# boost_stage_HP.net
KiCad netlist of a schematic drawn in Altium Designer
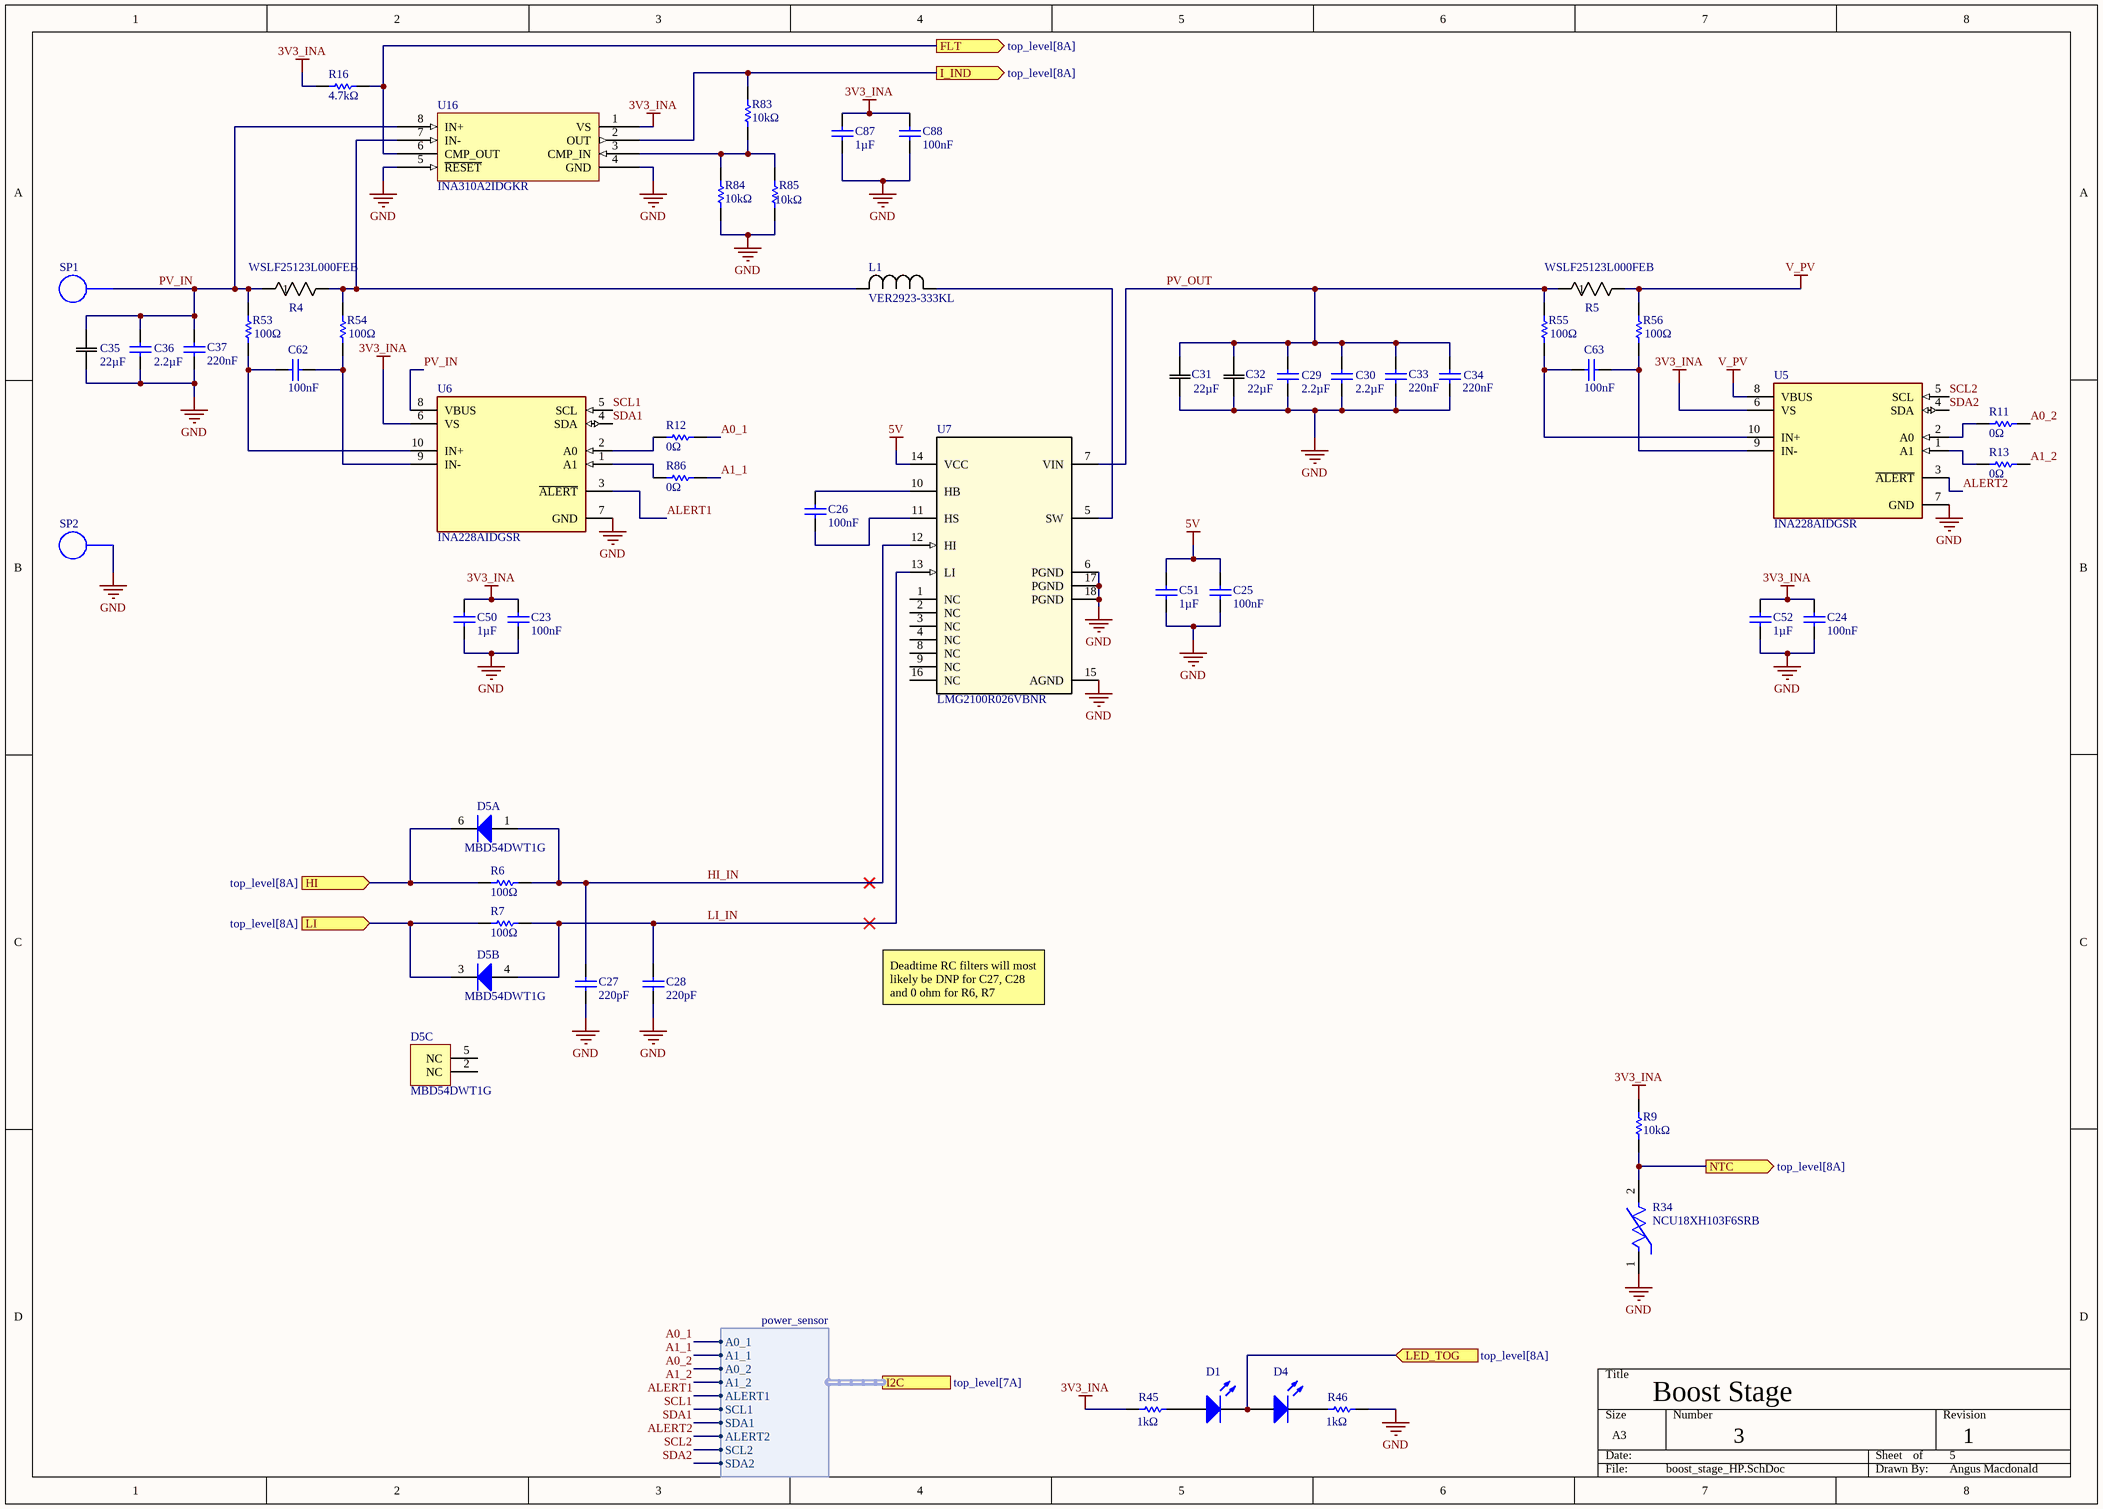
[diagram p0: boost_stage_HP.SchDoc]

(export (version "E")
  (design (tool "Eeschema 10.0.6"))
  (components
    (comp (ref "C23")
      (value "100nF")
      (footprint "C0603")
      (description "25V 100nF X7R ±10% 0603 Multilayer Ceramic Capacitors MLCC - SMD/SMT ROHS")
      (fields (field (name "TOLERANCE") "10%") (field (name "VOLTAGE") "25V"))
      (libsource (lib "Sunswift Racing") (part "Capacitor"))
    )
    (comp (ref "C24")
      (value "100nF")
      (footprint "C0603")
      (description "25V 100nF X7R ±10% 0603 Multilayer Ceramic Capacitors MLCC - SMD/SMT ROHS")
      (fields (field (name "TOLERANCE") "10%") (field (name "VOLTAGE") "25V"))
      (libsource (lib "Sunswift Racing") (part "Capacitor"))
    )
    (comp (ref "C25")
      (value "100nF")
      (footprint "C0603")
      (description "25V 100nF X7R ±10% 0603 Multilayer Ceramic Capacitors MLCC - SMD/SMT ROHS")
      (fields (field (name "TOLERANCE") "10%") (field (name "VOLTAGE") "25V"))
      (libsource (lib "Sunswift Racing") (part "Capacitor"))
    )
    (comp (ref "C26")
      (value "100nF")
      (footprint "C0603")
      (description "25V 100nF X7R ±10% 0603 Multilayer Ceramic Capacitors MLCC - SMD/SMT ROHS")
      (fields (field (name "TOLERANCE") "10%") (field (name "VOLTAGE") "25V"))
      (libsource (lib "Sunswift Racing") (part "Capacitor"))
    )
    (comp (ref "C27")
      (value "220pF")
      (footprint "C0603")
      (description "50V 220pF NP0 ±5% 0603 Multilayer Ceramic Capacitors MLCC - SMD/SMT ROHS")
      (fields (field (name "VOLTAGE") "50V") (field (name "TOLERANCE") "5%"))
      (libsource (lib "Sunswift Racing") (part "Capacitor"))
    )
    (comp (ref "C28")
      (value "220pF")
      (footprint "C0603")
      (description "50V 220pF NP0 ±5% 0603 Multilayer Ceramic Capacitors MLCC - SMD/SMT ROHS")
      (fields (field (name "VOLTAGE") "50V") (field (name "TOLERANCE") "5%"))
      (libsource (lib "Sunswift Racing") (part "Capacitor"))
    )
    (comp (ref "C29")
      (value "2.2µF")
      (footprint "FP-CC1206-1_25-IPC_B")
      (description "1206 2.2 uF 100 V ±10% Tolerance X7R SMT Multilayer Ceramic Chip Capacitor")
      (fields (field (name "TOLERANCE") "10%") (field (name "Comment") "CC1206KKX7R0BB225"))
      (libsource (lib "Sunswift Racing") (part "Copy of 11868f565c42a9108669ba33697ecf6"))
    )
    (comp (ref "C30")
      (value "2.2µF")
      (footprint "FP-CC1206-1_25-IPC_B")
      (description "1206 2.2 uF 100 V ±10% Tolerance X7R SMT Multilayer Ceramic Chip Capacitor")
      (fields (field (name "TOLERANCE") "10%") (field (name "Comment") "CC1206KKX7R0BB225"))
      (libsource (lib "Sunswift Racing") (part "Copy of 11868f565c42a9108669ba33697ecf6"))
    )
    (comp (ref "C31")
      (value "22µF")
      (footprint "CAP_EEE-FK2A220P_PAN")
      (description "Radial Can - SMD ALUMINUM ELECTROLYTIC CAPACITOR FK 100V 22muF ±20% 0.315Dia 8.00mm")
      (fields
        (field (name "TOLERANCE") "20%")
        (field (name "MANUFACTURER_PART_NUMBER") "EEE-FK2A220P")
        (field (name "COPYRIGHT") "Copyright (C) 2025 Ultra Librarian. All rights reserved.")
      )
      (libsource (lib "Sunswift Racing") (part "EEE-FK2A220P"))
    )
    (comp (ref "C32")
      (value "22µF")
      (footprint "CAP_EEE-FK2A220P_PAN")
      (description "Radial Can - SMD ALUMINUM ELECTROLYTIC CAPACITOR FK 100V 22muF ±20% 0.315Dia 8.00mm")
      (fields
        (field (name "TOLERANCE") "20%")
        (field (name "MANUFACTURER_PART_NUMBER") "EEE-FK2A220P")
        (field (name "COPYRIGHT") "Copyright (C) 2025 Ultra Librarian. All rights reserved.")
      )
      (libsource (lib "Sunswift Racing") (part "EEE-FK2A220P"))
    )
    (comp (ref "C33")
      (value "220nF")
      (footprint "C0805")
      (description "Multilayer Ceramic Capacitors MLCC - SMD/SMT 100V 0.22uF X7R 0805 10%")
      (fields
        (field (name "TOLERANCE") "10%")
        (field (name "MANUFACTURER PART NUMBER") "C2012X5R1A336M125AC")
      )
      (libsource (lib "Sunswift Racing") (part "Capacitor"))
    )
    (comp (ref "C34")
      (value "220nF")
      (footprint "C0805")
      (description "Multilayer Ceramic Capacitors MLCC - SMD/SMT 100V 0.22uF X7R 0805 10%")
      (fields
        (field (name "TOLERANCE") "10%")
        (field (name "MANUFACTURER PART NUMBER") "C2012X5R1A336M125AC")
      )
      (libsource (lib "Sunswift Racing") (part "Capacitor"))
    )
    (comp (ref "C35")
      (value "22µF")
      (footprint "CAP_EEE-FK2A220P_PAN")
      (description "Radial Can - SMD ALUMINUM ELECTROLYTIC CAPACITOR FK 100V 22muF ±20% 0.315Dia 8.00mm")
      (fields
        (field (name "TOLERANCE") "20%")
        (field (name "MANUFACTURER_PART_NUMBER") "EEE-FK2A220P")
        (field (name "COPYRIGHT") "Copyright (C) 2025 Ultra Librarian. All rights reserved.")
      )
      (libsource (lib "Sunswift Racing") (part "EEE-FK2A220P"))
    )
    (comp (ref "C36")
      (value "2.2µF")
      (footprint "FP-CC1206-1_25-IPC_B")
      (description "1206 2.2 uF 100 V ±10% Tolerance X7R SMT Multilayer Ceramic Chip Capacitor")
      (fields (field (name "TOLERANCE") "10%") (field (name "Comment") "CC1206KKX7R0BB225"))
      (libsource (lib "Sunswift Racing") (part "Copy of 11868f565c42a9108669ba33697ecf6"))
    )
    (comp (ref "C37")
      (value "220nF")
      (footprint "C0805")
      (description "Multilayer Ceramic Capacitors MLCC - SMD/SMT 100V 0.22uF X7R 0805 10%")
      (fields
        (field (name "TOLERANCE") "10%")
        (field (name "MANUFACTURER PART NUMBER") "C2012X5R1A336M125AC")
      )
      (libsource (lib "Sunswift Racing") (part "Capacitor"))
    )
    (comp (ref "C50")
      (value "1µF")
      (footprint "C0603")
      (description "16V 1uF X7R ±10% 0603 Multilayer Ceramic Capacitors MLCC - SMD/SMT ROHS")
      (fields (field (name "VOLTAGE") "16V") (field (name "TOLERANCE") "10%"))
      (libsource (lib "Sunswift Racing") (part "Capacitor"))
    )
    (comp (ref "C51")
      (value "1µF")
      (footprint "C0603")
      (description "16V 1uF X7R ±10% 0603 Multilayer Ceramic Capacitors MLCC - SMD/SMT ROHS")
      (fields (field (name "VOLTAGE") "16V") (field (name "TOLERANCE") "10%"))
      (libsource (lib "Sunswift Racing") (part "Capacitor"))
    )
    (comp (ref "C52")
      (value "1µF")
      (footprint "C0603")
      (description "16V 1uF X7R ±10% 0603 Multilayer Ceramic Capacitors MLCC - SMD/SMT ROHS")
      (fields (field (name "VOLTAGE") "16V") (field (name "TOLERANCE") "10%"))
      (libsource (lib "Sunswift Racing") (part "Capacitor"))
    )
    (comp (ref "C62")
      (value "100nF")
      (footprint "C0603")
      (description "Ceramic Capacitor, Ceramic, 100V, 5% +Tol, 5% -Tol, X7R, 0.15 TC, 0.1uF, Surface Mount, 0603")
      (fields (field (name "Comment") "CC0603JRX7R0BB104"))
      (libsource (lib "Sunswift Racing") (part "Capacitor"))
    )
    (comp (ref "C63")
      (value "100nF")
      (footprint "C0603")
      (description "Ceramic Capacitor, Ceramic, 100V, 5% +Tol, 5% -Tol, X7R, 0.15 TC, 0.1uF, Surface Mount, 0603")
      (fields (field (name "Comment") "CC0603JRX7R0BB104"))
      (libsource (lib "Sunswift Racing") (part "Capacitor"))
    )
    (comp (ref "C87")
      (value "1µF")
      (footprint "C0603")
      (description "16V 1uF X7R ±10% 0603 Multilayer Ceramic Capacitors MLCC - SMD/SMT ROHS")
      (fields (field (name "VOLTAGE") "16V") (field (name "TOLERANCE") "10%"))
      (libsource (lib "Sunswift Racing") (part "Capacitor"))
    )
    (comp (ref "C88")
      (value "100nF")
      (footprint "C0603")
      (description "25V 100nF X7R ±10% 0603 Multilayer Ceramic Capacitors MLCC - SMD/SMT ROHS")
      (fields (field (name "TOLERANCE") "10%") (field (name "VOLTAGE") "25V"))
      (libsource (lib "Sunswift Racing") (part "Capacitor"))
    )
    (comp (ref "D1")
      (value "LED EMERALD 0805")
      (footprint "0805 LED")
      (description "Emerald 0805  Light Emitting Diodes (LED) ROHS GREEN JLCPCB PICK&PLACE")
      (fields (field (name "MFR.PART #") "C2297") (field (name "MANUFACTURER") "Hubei KENTO Elec"))
      (libsource (lib "Sunswift Racing") (part "LED 0805-Symbol-1"))
    )
    (comp (ref "D4")
      (value "LED RED 0805")
      (footprint "0805 LED")
      (description "Red 0805  Light Emitting Diodes (LED) ROHS JLCPCB PICK&PLACE")
      (fields
        (field (name "MANUFACTURER") "Foshan NationStar Optoelectronics")
        (field (name "JLCPCB PART #") "C84256")
      )
      (libsource (lib "Sunswift Racing") (part "LED 0805-Symbol-1"))
    )
    (comp (ref "D5")
      (value "MBD54DWT1G")
      (footprint "ONSC-SOT-363-6-419B-02_W_V")
      (description "MBD54DWT1G Series 30 V 600 mA Dual Schottky Barrier Diode - SOT-363")
      (libsource (lib "") (part "ONSC-SBD-A1K3A4K6-6_1"))
    )
    (comp (ref "L1")
      (value "VER2923-333KL")
      (footprint "IND_VER2923_COC")
      (description "Description")
      (fields (field (name "COPYRIGHT") "Copyright (C) 2026 Ultra Librarian. All rights reserved."))
      (libsource (lib "Sunswift Racing") (part "VER2923-333KL"))
    )
    (comp (ref "R4")
      (value "WSLF25123L000FEB")
      (footprint "RES_3L000FEB_VIS")
      (description "WSLF2512 .003 1% EB e3")
      (fields (field (name "COPYRIGHT") "Copyright (C) 2026 Ultra Librarian. All rights reserved."))
      (libsource (lib "Sunswift Racing") (part "WSLF25123L000FEB"))
    )
    (comp (ref "R5")
      (value "WSLF25123L000FEB")
      (footprint "RES_3L000FEB_VIS")
      (description "WSLF2512 .003 1% EB e3")
      (fields (field (name "COPYRIGHT") "Copyright (C) 2026 Ultra Librarian. All rights reserved."))
      (libsource (lib "Sunswift Racing") (part "WSLF25123L000FEB"))
    )
    (comp (ref "R6")
      (value "100Ω")
      (footprint "RESC1608X55X25ML10T15")
      (description "Yageo RC0603FR-07100RL 0603 SMD Resistor 100 Ohm thin film chip resistor")
      (fields (field (name "TOLERANCE") "1%") (field (name "Comment") "RC0603FR-07100RL"))
      (libsource (lib "Sunswift Racing") (part "RES-2"))
    )
    (comp (ref "R7")
      (value "100Ω")
      (footprint "RESC1608X55X25ML10T15")
      (description "Yageo RC0603FR-07100RL 0603 SMD Resistor 100 Ohm thin film chip resistor")
      (fields (field (name "TOLERANCE") "1%") (field (name "Comment") "RC0603FR-07100RL"))
      (libsource (lib "Sunswift Racing") (part "RES-2"))
    )
    (comp (ref "R9")
      (value "10kΩ")
      (footprint "RESC1608X55X25ML10T15")
      (description "10 kOhms ±1% 0.1W, 1/10W Chip Resistor 0603 (1608 Metric) Moisture Resistant Thick Film")
      (fields (field (name "TOLERANCE") "1%") (field (name "Comment") "RC0603FR-0710KL"))
      (libsource (lib "Sunswift Racing") (part "RES-2"))
    )
    (comp (ref "R11")
      (value "0Ω")
      (footprint "RESC1608X55X25ML10T15")
      (description "GENERAL PURPOSE CHIP RESISTOR Metal Glaze/thick Film, 0.1W, 0ohm, Surface Mount, 0603")
      (fields (field (name "TOLERANCE") "1%") (field (name "Comment") "RC0603JR-070RL"))
      (libsource (lib "Sunswift Racing") (part "RES-2"))
    )
    (comp (ref "R12")
      (value "0Ω")
      (footprint "RESC1608X55X25ML10T15")
      (description "GENERAL PURPOSE CHIP RESISTOR Metal Glaze/thick Film, 0.1W, 0ohm, Surface Mount, 0603")
      (fields (field (name "TOLERANCE") "1%") (field (name "Comment") "RC0603JR-070RL"))
      (libsource (lib "Sunswift Racing") (part "RES-2"))
    )
    (comp (ref "R13")
      (value "0Ω")
      (footprint "RESC1608X55X25ML10T15")
      (description "GENERAL PURPOSE CHIP RESISTOR Metal Glaze/thick Film, 0.1W, 0ohm, Surface Mount, 0603")
      (fields (field (name "TOLERANCE") "1%") (field (name "Comment") "RC0603JR-070RL"))
      (libsource (lib "Sunswift Racing") (part "RES-2"))
    )
    (comp (ref "R16")
      (value "4.7kΩ")
      (footprint "RESC1608X55X25ML10T15")
      (description "Yageo RC0603FR-074K7L Resistor 0603 SMD 4.7k Ohm 1% 100mW Thick Film")
      (fields (field (name "TOLERANCE") "1%") (field (name "Comment") "RC0603FR-074K7L"))
      (libsource (lib "Sunswift Racing") (part "RES-2"))
    )
    (comp (ref "R34")
      (value "NCU18XH103F6SRB")
      (footprint "FP-NCU18-0_15-IPC_A")
      (description "NTC Thermistors; MURATA; NCU18XH103F6SRB; 10 kOhm; 1 %; 0603; 950 µm")
      (fields (field (name "TOLERANCE") "1%"))
      (libsource (lib "Sunswift Racing") (part "3b148a6ebabc5fb4d708a66c052d352"))
    )
    (comp (ref "R45")
      (value "1kΩ")
      (footprint "RESC1608X55X25ML10T15")
      (description "1 kOhms ±1% 0.1W, 1/10W Chip Resistor 0603 (1608 Metric) Moisture Resistant Thick Film")
      (fields (field (name "TOLERANCE") "1%") (field (name "Comment") "RC0603FR-101KL"))
      (libsource (lib "Sunswift Racing") (part "RES-2"))
    )
    (comp (ref "R46")
      (value "1kΩ")
      (footprint "RESC1608X55X25ML10T15")
      (description "1 kOhms ±1% 0.1W, 1/10W Chip Resistor 0603 (1608 Metric) Moisture Resistant Thick Film")
      (fields (field (name "TOLERANCE") "1%") (field (name "Comment") "RC0603FR-101KL"))
      (libsource (lib "Sunswift Racing") (part "RES-2"))
    )
    (comp (ref "R53")
      (value "100Ω")
      (footprint "RESC1608X55X25ML10T15")
      (description "Yageo RC0603FR-07100RL 0603 SMD Resistor 100 Ohm thin film chip resistor")
      (fields (field (name "TOLERANCE") "1%") (field (name "Comment") "RC0603FR-07100RL"))
      (libsource (lib "Sunswift Racing") (part "RES-2"))
    )
    (comp (ref "R54")
      (value "100Ω")
      (footprint "RESC1608X55X25ML10T15")
      (description "Yageo RC0603FR-07100RL 0603 SMD Resistor 100 Ohm thin film chip resistor")
      (fields (field (name "TOLERANCE") "1%") (field (name "Comment") "RC0603FR-07100RL"))
      (libsource (lib "Sunswift Racing") (part "RES-2"))
    )
    (comp (ref "R55")
      (value "100Ω")
      (footprint "RESC1608X55X25ML10T15")
      (description "Yageo RC0603FR-07100RL 0603 SMD Resistor 100 Ohm thin film chip resistor")
      (fields (field (name "TOLERANCE") "1%") (field (name "Comment") "RC0603FR-07100RL"))
      (libsource (lib "Sunswift Racing") (part "RES-2"))
    )
    (comp (ref "R56")
      (value "100Ω")
      (footprint "RESC1608X55X25ML10T15")
      (description "Yageo RC0603FR-07100RL 0603 SMD Resistor 100 Ohm thin film chip resistor")
      (fields (field (name "TOLERANCE") "1%") (field (name "Comment") "RC0603FR-07100RL"))
      (libsource (lib "Sunswift Racing") (part "RES-2"))
    )
    (comp (ref "R83")
      (value "10kΩ")
      (footprint "RESC1608X55X25ML10T15")
      (description "10 kOhms ±1% 0.1W, 1/10W Chip Resistor 0603 (1608 Metric) Moisture Resistant Thick Film")
      (fields (field (name "TOLERANCE") "1%") (field (name "Comment") "RC0603FR-0710KL"))
      (libsource (lib "Sunswift Racing") (part "RES-2"))
    )
    (comp (ref "R84")
      (value "10kΩ")
      (footprint "RESC1608X55X25ML10T15")
      (description "10 kOhms ±1% 0.1W, 1/10W Chip Resistor 0603 (1608 Metric) Moisture Resistant Thick Film")
      (fields (field (name "TOLERANCE") "1%") (field (name "Comment") "RC0603FR-0710KL"))
      (libsource (lib "Sunswift Racing") (part "RES-2"))
    )
    (comp (ref "R85")
      (value "10kΩ")
      (footprint "RESC1608X55X25ML10T15")
      (description "10 kOhms ±1% 0.1W, 1/10W Chip Resistor 0603 (1608 Metric) Moisture Resistant Thick Film")
      (fields (field (name "TOLERANCE") "1%") (field (name "Comment") "RC0603FR-0710KL"))
      (libsource (lib "Sunswift Racing") (part "RES-2"))
    )
    (comp (ref "R86")
      (value "0Ω")
      (footprint "RESC1608X55X25ML10T15")
      (description "GENERAL PURPOSE CHIP RESISTOR Metal Glaze/thick Film, 0.1W, 0ohm, Surface Mount, 0603")
      (fields (field (name "TOLERANCE") "1%") (field (name "Comment") "RC0603JR-070RL"))
      (libsource (lib "Sunswift Racing") (part "RES-2"))
    )
    (comp (ref "SP1")
      (value "Solder Pad")
      (footprint "Solder Pad-Footprint-1")
      (description "64mm^2 solder pad for wire to board connections,")
      (libsource (lib "Sunswift Racing") (part "Solder Pad-Symbol-1"))
    )
    (comp (ref "SP2")
      (value "Solder Pad")
      (footprint "Solder Pad-Footprint-1")
      (description "64mm^2 solder pad for wire to board connections,")
      (libsource (lib "Sunswift Racing") (part "Solder Pad-Symbol-1"))
    )
    (comp (ref "U5")
      (value "INA228AIDGSR")
      (footprint "FP-DGS0010A-IPC_C")
      (description "General Purpose Amplifiers; INA228AIDGSR; TEXAS INSTRUMENTS; 10; 3 mm; 3 mm; 5.5 V")
      (libsource (lib "Sunswift Racing") (part "1af3035f59f546649392dbf5608e80d"))
    )
    (comp (ref "U6")
      (value "INA228AIDGSR")
      (footprint "FP-DGS0010A-IPC_C")
      (description "General Purpose Amplifiers; INA228AIDGSR; TEXAS INSTRUMENTS; 10; 3 mm; 3 mm; 5.5 V")
      (libsource (lib "Sunswift Racing") (part "1af3035f59f546649392dbf5608e80d"))
    )
    (comp (ref "U7")
      (value "LMG2100R026VBNR")
      (footprint "VBN0018A-MFG")
      (description "100V 2.6mâ„")
      (fields (field (name "COPYRIGHT") "Copyright (C) 2025 Ultra Librarian. All rights reserved."))
      (libsource (lib "Sunswift Racing") (part "LMG2100R026VBNR"))
    )
    (comp (ref "U16")
      (value "INA310A2IDGKR")
      (footprint "VSSOP8_DGK_TEX")
      (description "-4-V to 110-V, 1.3-MHz, ultra-precise current-sense amplifier with comparator 8-VSSOP -40 to 125")
      (fields (field (name "COPYRIGHT") "Copyright (C) 2025 Ultra Librarian. All rights reserved."))
      (libsource (lib "Sunswift Racing") (part "INA310A2IDGKR"))
    )
  )
  (nets
    (net (code "2") (name "/A0_1") (class "Default")
      (node (ref "R12") (pin "1") (pinfunction "1_1") (pintype "passive"))
    )
    (net (code "3") (name "/A0_2") (class "Default")
      (node (ref "R11") (pin "2") (pinfunction "2_2") (pintype "passive"))
    )
    (net (code "4") (name "/A1_1") (class "Default")
      (node (ref "R86") (pin "1") (pinfunction "1_1") (pintype "passive"))
    )
    (net (code "5") (name "/A1_2") (class "Default")
      (node (ref "R13") (pin "2") (pinfunction "2_2") (pintype "passive"))
    )
    (net (code "6") (name "/ALERT1") (class "Default")
      (node (ref "U6") (pin "3") (pinfunction "~{ALERT}_3") (pintype "open_collector"))
    )
    (net (code "7") (name "/ALERT2") (class "Default")
      (node (ref "U5") (pin "3") (pinfunction "~{ALERT}_3") (pintype "open_collector"))
    )
    (net (code "8") (name "/FLT") (class "Default")
      (node (ref "R16") (pin "1") (pinfunction "1_1") (pintype "passive"))
      (node (ref "U16") (pin "6") (pinfunction "CMP_OUT_6") (pintype "passive"))
    )
    (net (code "9") (name "/HI") (class "Default")
      (node (ref "D5") (pin "6") (pinfunction "K2_6") (pintype "passive"))
      (node (ref "R6") (pin "2") (pinfunction "2_2") (pintype "passive"))
    )
    (net (code "10") (name "/HI_IN") (class "Default")
      (node (ref "C27") (pin "2") (pinfunction "2_2") (pintype "passive"))
      (node (ref "D5") (pin "1") (pinfunction "A2_1") (pintype "passive"))
      (node (ref "R6") (pin "1") (pinfunction "1_1") (pintype "passive"))
      (node (ref "U7") (pin "12") (pinfunction "HI_12") (pintype "input"))
    )
    (net (code "11") (name "/I_IND") (class "Default")
      (node (ref "R83") (pin "2") (pinfunction "2_2") (pintype "passive"))
      (node (ref "U16") (pin "2") (pinfunction "OUT_2") (pintype "output"))
    )
    (net (code "12") (name "/LED_TOG") (class "Default")
      (node (ref "D1") (pin "K") (pinfunction "K_K") (pintype "passive"))
      (node (ref "D4") (pin "A") (pinfunction "A_A") (pintype "passive"))
    )
    (net (code "13") (name "/LI") (class "Default")
      (node (ref "D5") (pin "3") (pinfunction "K1_3") (pintype "passive"))
      (node (ref "R7") (pin "2") (pinfunction "2_2") (pintype "passive"))
    )
    (net (code "14") (name "/LI_IN") (class "Default")
      (node (ref "C28") (pin "2") (pinfunction "2_2") (pintype "passive"))
      (node (ref "D5") (pin "4") (pinfunction "A1_4") (pintype "passive"))
      (node (ref "R7") (pin "1") (pinfunction "1_1") (pintype "passive"))
      (node (ref "U7") (pin "13") (pinfunction "LI_13") (pintype "input"))
    )
    (net (code "15") (name "/NTC") (class "Default")
      (node (ref "R34") (pin "2") (pinfunction "2_2") (pintype "passive"))
      (node (ref "R9") (pin "1") (pinfunction "1_1") (pintype "passive"))
    )
    (net (code "16") (name "/PV_IN") (class "Default")
      (node (ref "C35") (pin "2") (pinfunction "2_2") (pintype "passive"))
      (node (ref "C36") (pin "1") (pinfunction "1_1") (pintype "passive"))
      (node (ref "C37") (pin "2") (pinfunction "2_2") (pintype "passive"))
      (node (ref "R4") (pin "1") (pinfunction "1_1") (pintype "passive"))
      (node (ref "R53") (pin "2") (pinfunction "2_2") (pintype "passive"))
      (node (ref "SP1") (pin "SP") (pinfunction "Solder_Pad_SP") (pintype "power_in"))
      (node (ref "U16") (pin "8") (pinfunction "IN+_8") (pintype "input"))
      (node (ref "U6") (pin "8") (pinfunction "VBUS_8") (pintype "power_in"))
    )
    (net (code "17") (name "/PV_OUT") (class "Default")
      (node (ref "C29") (pin "1") (pinfunction "1_1") (pintype "passive"))
      (node (ref "C30") (pin "1") (pinfunction "1_1") (pintype "passive"))
      (node (ref "C31") (pin "2") (pinfunction "2_2") (pintype "passive"))
      (node (ref "C32") (pin "2") (pinfunction "2_2") (pintype "passive"))
      (node (ref "C33") (pin "2") (pinfunction "2_2") (pintype "passive"))
      (node (ref "C34") (pin "2") (pinfunction "2_2") (pintype "passive"))
      (node (ref "R5") (pin "1") (pinfunction "1_1") (pintype "passive"))
      (node (ref "R55") (pin "2") (pinfunction "2_2") (pintype "passive"))
      (node (ref "U7") (pin "7") (pinfunction "VIN_7") (pintype "power_in"))
    )
    (net (code "18") (name "/SCL1") (class "Default")
      (node (ref "U6") (pin "5") (pinfunction "SCL_5") (pintype "input"))
    )
    (net (code "19") (name "/SCL2") (class "Default")
      (node (ref "U5") (pin "5") (pinfunction "SCL_5") (pintype "input"))
    )
    (net (code "20") (name "/SDA1") (class "Default")
      (node (ref "U6") (pin "4") (pinfunction "SDA_4") (pintype "bidirectional"))
    )
    (net (code "21") (name "/SDA2") (class "Default")
      (node (ref "U5") (pin "4") (pinfunction "SDA_4") (pintype "bidirectional"))
    )
    (net (code "23") (name "3V3_INA") (class "Default")
      (node (ref "C23") (pin "2") (pinfunction "2_2") (pintype "passive"))
      (node (ref "C24") (pin "2") (pinfunction "2_2") (pintype "passive"))
      (node (ref "C50") (pin "2") (pinfunction "2_2") (pintype "passive"))
      (node (ref "C52") (pin "2") (pinfunction "2_2") (pintype "passive"))
      (node (ref "C87") (pin "2") (pinfunction "2_2") (pintype "passive"))
      (node (ref "C88") (pin "2") (pinfunction "2_2") (pintype "passive"))
      (node (ref "R16") (pin "2") (pinfunction "2_2") (pintype "passive"))
      (node (ref "R45") (pin "1") (pinfunction "1_1") (pintype "passive"))
      (node (ref "R9") (pin "2") (pinfunction "2_2") (pintype "passive"))
      (node (ref "U16") (pin "1") (pinfunction "VS_1") (pintype "power_in"))
      (node (ref "U5") (pin "6") (pinfunction "VS_6") (pintype "power_in"))
      (node (ref "U6") (pin "6") (pinfunction "VS_6") (pintype "power_in"))
    )
    (net (code "24") (name "5V") (class "Default")
      (node (ref "C25") (pin "2") (pinfunction "2_2") (pintype "passive"))
      (node (ref "C51") (pin "2") (pinfunction "2_2") (pintype "passive"))
      (node (ref "U7") (pin "14") (pinfunction "VCC_14") (pintype "power_in"))
    )
    (net (code "25") (name "GND") (class "Default")
      (node (ref "C23") (pin "1") (pinfunction "1_1") (pintype "passive"))
      (node (ref "C24") (pin "1") (pinfunction "1_1") (pintype "passive"))
      (node (ref "C25") (pin "1") (pinfunction "1_1") (pintype "passive"))
      (node (ref "C27") (pin "1") (pinfunction "1_1") (pintype "passive"))
      (node (ref "C28") (pin "1") (pinfunction "1_1") (pintype "passive"))
      (node (ref "C29") (pin "2") (pinfunction "2_2") (pintype "passive"))
      (node (ref "C30") (pin "2") (pinfunction "2_2") (pintype "passive"))
      (node (ref "C31") (pin "1") (pinfunction "1_1") (pintype "passive"))
      (node (ref "C32") (pin "1") (pinfunction "1_1") (pintype "passive"))
      (node (ref "C33") (pin "1") (pinfunction "1_1") (pintype "passive"))
      (node (ref "C34") (pin "1") (pinfunction "1_1") (pintype "passive"))
      (node (ref "C35") (pin "1") (pinfunction "1_1") (pintype "passive"))
      (node (ref "C36") (pin "2") (pinfunction "2_2") (pintype "passive"))
      (node (ref "C37") (pin "1") (pinfunction "1_1") (pintype "passive"))
      (node (ref "C50") (pin "1") (pinfunction "1_1") (pintype "passive"))
      (node (ref "C51") (pin "1") (pinfunction "1_1") (pintype "passive"))
      (node (ref "C52") (pin "1") (pinfunction "1_1") (pintype "passive"))
      (node (ref "C87") (pin "1") (pinfunction "1_1") (pintype "passive"))
      (node (ref "C88") (pin "1") (pinfunction "1_1") (pintype "passive"))
      (node (ref "R34") (pin "1") (pinfunction "1_1") (pintype "passive"))
      (node (ref "R46") (pin "2") (pinfunction "2_2") (pintype "passive"))
      (node (ref "R84") (pin "1") (pinfunction "1_1") (pintype "passive"))
      (node (ref "R85") (pin "1") (pinfunction "1_1") (pintype "passive"))
      (node (ref "SP2") (pin "SP") (pinfunction "Solder_Pad_SP") (pintype "power_in"))
      (node (ref "U16") (pin "4") (pinfunction "GND_4") (pintype "power_in"))
      (node (ref "U16") (pin "5") (pinfunction "~{RESET}_5") (pintype "input"))
      (node (ref "U5") (pin "7") (pinfunction "GND_7") (pintype "power_in"))
      (node (ref "U6") (pin "7") (pinfunction "GND_7") (pintype "power_in"))
      (node (ref "U7") (pin "15") (pinfunction "AGND_15") (pintype "power_in"))
      (node (ref "U7") (pin "17") (pinfunction "PGND_17") (pintype "power_in"))
      (node (ref "U7") (pin "18") (pinfunction "PGND_18") (pintype "power_in"))
      (node (ref "U7") (pin "6") (pinfunction "PGND_6") (pintype "power_in"))
    )
    (net (code "26") (name "Net-(D1-PadA)") (class "Default")
      (node (ref "D1") (pin "A") (pinfunction "A_A") (pintype "passive"))
      (node (ref "R45") (pin "2") (pinfunction "2_2") (pintype "passive"))
    )
    (net (code "27") (name "Net-(D4-PadK)") (class "Default")
      (node (ref "D4") (pin "K") (pinfunction "K_K") (pintype "passive"))
      (node (ref "R46") (pin "1") (pinfunction "1_1") (pintype "passive"))
    )
    (net (code "28") (name "Net-(U5-A0)") (class "Default")
      (node (ref "R11") (pin "1") (pinfunction "1_1") (pintype "passive"))
      (node (ref "U5") (pin "2") (pinfunction "A0_2") (pintype "input"))
    )
    (net (code "29") (name "Net-(U5-A1)") (class "Default")
      (node (ref "R13") (pin "1") (pinfunction "1_1") (pintype "passive"))
      (node (ref "U5") (pin "1") (pinfunction "A1_1") (pintype "input"))
    )
    (net (code "30") (name "Net-(U5-IN+)") (class "Default")
      (node (ref "C63") (pin "2") (pinfunction "2_2") (pintype "passive"))
      (node (ref "R55") (pin "1") (pinfunction "1_1") (pintype "passive"))
      (node (ref "U5") (pin "10") (pinfunction "IN+_10") (pintype "passive"))
    )
    (net (code "31") (name "Net-(U5-IN-)") (class "Default")
      (node (ref "C63") (pin "1") (pinfunction "1_1") (pintype "passive"))
      (node (ref "R56") (pin "1") (pinfunction "1_1") (pintype "passive"))
      (node (ref "U5") (pin "9") (pinfunction "IN-_9") (pintype "passive"))
    )
    (net (code "32") (name "Net-(U6-A0)") (class "Default")
      (node (ref "R12") (pin "2") (pinfunction "2_2") (pintype "passive"))
      (node (ref "U6") (pin "2") (pinfunction "A0_2") (pintype "input"))
    )
    (net (code "33") (name "Net-(U6-A1)") (class "Default")
      (node (ref "R86") (pin "2") (pinfunction "2_2") (pintype "passive"))
      (node (ref "U6") (pin "1") (pinfunction "A1_1") (pintype "input"))
    )
    (net (code "34") (name "Net-(U6-IN+)") (class "Default")
      (node (ref "C62") (pin "2") (pinfunction "2_2") (pintype "passive"))
      (node (ref "R53") (pin "1") (pinfunction "1_1") (pintype "passive"))
      (node (ref "U6") (pin "10") (pinfunction "IN+_10") (pintype "passive"))
    )
    (net (code "35") (name "Net-(U6-IN-)") (class "Default")
      (node (ref "C62") (pin "1") (pinfunction "1_1") (pintype "passive"))
      (node (ref "R54") (pin "1") (pinfunction "1_1") (pintype "passive"))
      (node (ref "U6") (pin "9") (pinfunction "IN-_9") (pintype "passive"))
    )
    (net (code "36") (name "Net-(U7-HB)") (class "Default")
      (node (ref "C26") (pin "2") (pinfunction "2_2") (pintype "passive"))
      (node (ref "U7") (pin "10") (pinfunction "HB_10") (pintype "passive"))
    )
    (net (code "37") (name "Net-(U7-HS)") (class "Default")
      (node (ref "C26") (pin "1") (pinfunction "1_1") (pintype "passive"))
      (node (ref "U7") (pin "11") (pinfunction "HS_11") (pintype "passive"))
    )
    (net (code "38") (name "Net-(U7-SW)") (class "Default")
      (node (ref "L1") (pin "1") (pinfunction "1_1") (pintype "passive"))
      (node (ref "U7") (pin "5") (pinfunction "SW_5") (pintype "passive"))
    )
    (net (code "39") (name "Net-(U16-CMP_IN)") (class "Default")
      (node (ref "R83") (pin "1") (pinfunction "1_1") (pintype "passive"))
      (node (ref "R84") (pin "2") (pinfunction "2_2") (pintype "passive"))
      (node (ref "R85") (pin "2") (pinfunction "2_2") (pintype "passive"))
      (node (ref "U16") (pin "3") (pinfunction "CMP_IN_3") (pintype "input"))
    )
    (net (code "40") (name "Net-(U16-IN-)") (class "Default")
      (node (ref "L1") (pin "2") (pinfunction "2_2") (pintype "passive"))
      (node (ref "R4") (pin "2") (pinfunction "2_2") (pintype "passive"))
      (node (ref "R54") (pin "2") (pinfunction "2_2") (pintype "passive"))
      (node (ref "U16") (pin "7") (pinfunction "IN-_7") (pintype "input"))
    )
    (net (code "41") (name "V_PV") (class "Default")
      (node (ref "R5") (pin "2") (pinfunction "2_2") (pintype "passive"))
      (node (ref "R56") (pin "2") (pinfunction "2_2") (pintype "passive"))
      (node (ref "U5") (pin "8") (pinfunction "VBUS_8") (pintype "power_in"))
    )
    (net (code "42") (name "unconnected-(D5C-NC-Pad2)") (class "Default")
      (node (ref "D5") (pin "2") (pinfunction "NC_2") (pintype "passive"))
    )
    (net (code "43") (name "unconnected-(D5C-NC-Pad5)") (class "Default")
      (node (ref "D5") (pin "5") (pinfunction "NC_5") (pintype "passive"))
    )
    (net (code "44") (name "unconnected-(U7-NC-Pad1)") (class "Default")
      (node (ref "U7") (pin "1") (pinfunction "NC_1") (pintype "passive"))
    )
    (net (code "45") (name "unconnected-(U7-NC-Pad2)") (class "Default")
      (node (ref "U7") (pin "2") (pinfunction "NC_2") (pintype "passive"))
    )
    (net (code "46") (name "unconnected-(U7-NC-Pad3)") (class "Default")
      (node (ref "U7") (pin "3") (pinfunction "NC_3") (pintype "passive"))
    )
    (net (code "47") (name "unconnected-(U7-NC-Pad4)") (class "Default")
      (node (ref "U7") (pin "4") (pinfunction "NC_4") (pintype "passive"))
    )
    (net (code "48") (name "unconnected-(U7-NC-Pad8)") (class "Default")
      (node (ref "U7") (pin "8") (pinfunction "NC_8") (pintype "passive"))
    )
    (net (code "49") (name "unconnected-(U7-NC-Pad9)") (class "Default")
      (node (ref "U7") (pin "9") (pinfunction "NC_9") (pintype "passive"))
    )
    (net (code "50") (name "unconnected-(U7-NC-Pad16)") (class "Default")
      (node (ref "U7") (pin "16") (pinfunction "NC_16") (pintype "passive"))
    )
  )
)
